# LED_PORT.net
KiCad netlist of a schematic drawn in Altium Designer
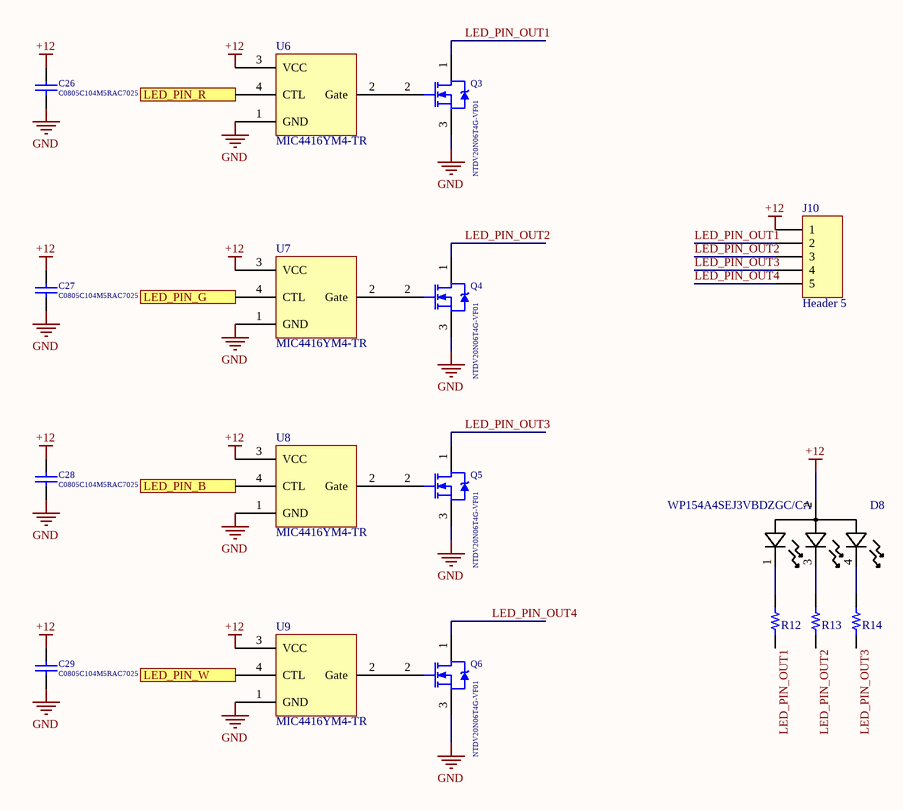
[diagram p0: LED_PORT.SchDoc]

(export (version "E")
  (design (tool "Eeschema 10.0.6"))
  (components
    (comp (ref "C26")
      (value "C0805C104M5RAC7025")
      (footprint "CAP SMD 0805")
      (description "0.1 µF ±20% 50V Ceramic Capacitor X7R 0805 (2012 Metric)")
      (fields (field (name "PUBLISHER") "Altium Limited"))
      (libsource (lib "DIY-USB Led Controller") (part "Cap_3_1"))
    )
    (comp (ref "C27")
      (value "C0805C104M5RAC7025")
      (footprint "CAP SMD 0805")
      (description "0.1 µF ±20% 50V Ceramic Capacitor X7R 0805 (2012 Metric)")
      (fields (field (name "PUBLISHER") "Altium Limited"))
      (libsource (lib "DIY-USB Led Controller") (part "Cap_3_1"))
    )
    (comp (ref "C28")
      (value "C0805C104M5RAC7025")
      (footprint "CAP SMD 0805")
      (description "0.1 µF ±20% 50V Ceramic Capacitor X7R 0805 (2012 Metric)")
      (fields (field (name "PUBLISHER") "Altium Limited"))
      (libsource (lib "DIY-USB Led Controller") (part "Cap_3_1"))
    )
    (comp (ref "C29")
      (value "C0805C104M5RAC7025")
      (footprint "CAP SMD 0805")
      (description "0.1 µF ±20% 50V Ceramic Capacitor X7R 0805 (2012 Metric)")
      (fields (field (name "PUBLISHER") "Altium Limited"))
      (libsource (lib "DIY-USB Led Controller") (part "Cap_3_1"))
    )
    (comp (ref "D8")
      (value "WP154A4SEJ3VBDZGC/CA")
      (footprint "LED_RGB_5MM")
      (description "5mm RGB Tri-Color Round Lamp")
      (fields (field (name "COPYRIGHT") "Copyright (C) 2022 Ultra Librarian. All rights reserved."))
      (libsource (lib "WP154A4SEJ3VBDZGC&slash_CA") (part "WP154A4SEJ3VBDZGC/CA"))
    )
    (comp (ref "J10")
      (value "Header 5")
      (footprint "CONN. 5")
      (fields (field (name "PUBLISHER") "Altium Limited"))
      (libsource (lib "DIY-USB Led Controller") (part "TermBlock 5"))
    )
    (comp (ref "Q3")
      (value "NTDV20N06T4G-VF01")
      (footprint "DPAK228P991X238-3N")
      (description "MOSFET N-CH 60V 20A DPAK")
      (fields
        (field (name "MANUFACTURE PART NUMBER") "IRF540N_R4942")
        (field (name "PUBLISHER") "Altium Limited")
      )
      (libsource (lib "HYD_EMER_2") (part "IRF540NS"))
    )
    (comp (ref "Q4")
      (value "NTDV20N06T4G-VF01")
      (footprint "DPAK228P991X238-3N")
      (description "MOSFET N-CH 60V 20A DPAK")
      (fields
        (field (name "MANUFACTURE PART NUMBER") "IRF540N_R4942")
        (field (name "PUBLISHER") "Altium Limited")
      )
      (libsource (lib "HYD_EMER_2") (part "IRF540NS"))
    )
    (comp (ref "Q5")
      (value "NTDV20N06T4G-VF01")
      (footprint "DPAK228P991X238-3N")
      (description "MOSFET N-CH 60V 20A DPAK")
      (fields
        (field (name "MANUFACTURE PART NUMBER") "IRF540N_R4942")
        (field (name "PUBLISHER") "Altium Limited")
      )
      (libsource (lib "HYD_EMER_2") (part "IRF540NS"))
    )
    (comp (ref "Q6")
      (value "NTDV20N06T4G-VF01")
      (footprint "DPAK228P991X238-3N")
      (description "MOSFET N-CH 60V 20A DPAK")
      (fields
        (field (name "MANUFACTURE PART NUMBER") "IRF540N_R4942")
        (field (name "PUBLISHER") "Altium Limited")
      )
      (libsource (lib "HYD_EMER_2") (part "IRF540NS"))
    )
    (comp (ref "R12")
      (value "1k")
      (footprint "RES SMD 0805")
      (description "RES SMD 1k OHM 1% 1/4W 0805")
      (libsource (lib "DIY-USB Led Controller") (part "RESISTOR"))
    )
    (comp (ref "R13")
      (value "1K")
      (footprint "RES SMD 0805")
      (description "RES SMD 1K OHM 1% 1/4W 0805")
      (libsource (lib "DIY-USB Led Controller") (part "RESISTOR_2"))
    )
    (comp (ref "R14")
      (value "1K")
      (footprint "RES SMD 0805")
      (description "RES SMD 1K OHM 1% 1/4W 0805")
      (libsource (lib "DIY-USB Led Controller") (part "RESISTOR_2"))
    )
    (comp (ref "U6")
      (value "MIC4416YM4-TR")
      (footprint "MICROCHIP SOT-143-4")
      (description "IC GATE DRVR LOW-SIDE SOT143")
      (fields (field (name "MANUFACTURER") "Microchip Technology"))
      (libsource (lib "Celestial Altium Library - altium_library") (part "MICROCHIP MIC4416"))
    )
    (comp (ref "U7")
      (value "MIC4416YM4-TR")
      (footprint "MICROCHIP SOT-143-4")
      (description "IC GATE DRVR LOW-SIDE SOT143")
      (fields (field (name "MANUFACTURER") "Microchip Technology"))
      (libsource (lib "Celestial Altium Library - altium_library") (part "MICROCHIP MIC4416"))
    )
    (comp (ref "U8")
      (value "MIC4416YM4-TR")
      (footprint "MICROCHIP SOT-143-4")
      (description "IC GATE DRVR LOW-SIDE SOT143")
      (fields (field (name "MANUFACTURER") "Microchip Technology"))
      (libsource (lib "Celestial Altium Library - altium_library") (part "MICROCHIP MIC4416"))
    )
    (comp (ref "U9")
      (value "MIC4416YM4-TR")
      (footprint "MICROCHIP SOT-143-4")
      (description "IC GATE DRVR LOW-SIDE SOT143")
      (fields (field (name "MANUFACTURER") "Microchip Technology"))
      (libsource (lib "Celestial Altium Library - altium_library") (part "MICROCHIP MIC4416"))
    )
  )
  (nets
    (net (code "1") (name "+12") (class "Default")
      (node (ref "C26") (pin "2") (pinfunction "2_2") (pintype "passive"))
      (node (ref "C27") (pin "2") (pinfunction "2_2") (pintype "passive"))
      (node (ref "C28") (pin "2") (pinfunction "2_2") (pintype "passive"))
      (node (ref "C29") (pin "2") (pinfunction "2_2") (pintype "passive"))
      (node (ref "D8") (pin "2") (pinfunction "2_2") (pintype "passive"))
      (node (ref "J10") (pin "1") (pinfunction "1_1") (pintype "passive"))
      (node (ref "U6") (pin "3") (pinfunction "VCC_3") (pintype "passive"))
      (node (ref "U7") (pin "3") (pinfunction "VCC_3") (pintype "passive"))
      (node (ref "U8") (pin "3") (pinfunction "VCC_3") (pintype "passive"))
      (node (ref "U9") (pin "3") (pinfunction "VCC_3") (pintype "passive"))
    )
    (net (code "2") (name "/LED_PIN_B") (class "Default")
      (node (ref "U8") (pin "4") (pinfunction "CTL_4") (pintype "passive"))
    )
    (net (code "3") (name "/LED_PIN_G") (class "Default")
      (node (ref "U7") (pin "4") (pinfunction "CTL_4") (pintype "passive"))
    )
    (net (code "4") (name "/LED_PIN_OUT1") (class "Default")
      (node (ref "J10") (pin "2") (pinfunction "2_2") (pintype "passive"))
      (node (ref "Q3") (pin "1") (pinfunction "D_1") (pintype "passive"))
      (node (ref "R12") (pin "1") (pinfunction "1_1") (pintype "passive"))
    )
    (net (code "5") (name "/LED_PIN_OUT2") (class "Default")
      (node (ref "J10") (pin "3") (pinfunction "3_3") (pintype "passive"))
      (node (ref "Q4") (pin "1") (pinfunction "D_1") (pintype "passive"))
      (node (ref "R13") (pin "1") (pinfunction "1_1") (pintype "passive"))
    )
    (net (code "6") (name "/LED_PIN_OUT3") (class "Default")
      (node (ref "J10") (pin "4") (pinfunction "4_4") (pintype "passive"))
      (node (ref "Q5") (pin "1") (pinfunction "D_1") (pintype "passive"))
      (node (ref "R14") (pin "1") (pinfunction "1_1") (pintype "passive"))
    )
    (net (code "7") (name "/LED_PIN_OUT4") (class "Default")
      (node (ref "J10") (pin "5") (pinfunction "5_5") (pintype "passive"))
      (node (ref "Q6") (pin "1") (pinfunction "D_1") (pintype "passive"))
    )
    (net (code "8") (name "/LED_PIN_R") (class "Default")
      (node (ref "U6") (pin "4") (pinfunction "CTL_4") (pintype "passive"))
    )
    (net (code "9") (name "/LED_PIN_W") (class "Default")
      (node (ref "U9") (pin "4") (pinfunction "CTL_4") (pintype "passive"))
    )
    (net (code "10") (name "GND") (class "Default")
      (node (ref "C26") (pin "1") (pinfunction "1_1") (pintype "passive"))
      (node (ref "C27") (pin "1") (pinfunction "1_1") (pintype "passive"))
      (node (ref "C28") (pin "1") (pinfunction "1_1") (pintype "passive"))
      (node (ref "C29") (pin "1") (pinfunction "1_1") (pintype "passive"))
      (node (ref "Q3") (pin "3") (pinfunction "S_3") (pintype "passive"))
      (node (ref "Q4") (pin "3") (pinfunction "S_3") (pintype "passive"))
      (node (ref "Q5") (pin "3") (pinfunction "S_3") (pintype "passive"))
      (node (ref "Q6") (pin "3") (pinfunction "S_3") (pintype "passive"))
      (node (ref "U6") (pin "1") (pinfunction "GND_1") (pintype "passive"))
      (node (ref "U7") (pin "1") (pinfunction "GND_1") (pintype "passive"))
      (node (ref "U8") (pin "1") (pinfunction "GND_1") (pintype "passive"))
      (node (ref "U9") (pin "1") (pinfunction "GND_1") (pintype "passive"))
    )
    (net (code "11") (name "Net-(D8-Pad1)") (class "Default")
      (node (ref "D8") (pin "1") (pinfunction "1_1") (pintype "passive"))
      (node (ref "R12") (pin "2") (pinfunction "2_2") (pintype "passive"))
    )
    (net (code "12") (name "Net-(D8-Pad3)") (class "Default")
      (node (ref "D8") (pin "3") (pinfunction "3_3") (pintype "passive"))
      (node (ref "R13") (pin "2") (pinfunction "2_2") (pintype "passive"))
    )
    (net (code "13") (name "Net-(D8-Pad4)") (class "Default")
      (node (ref "D8") (pin "4") (pinfunction "4_4") (pintype "passive"))
      (node (ref "R14") (pin "2") (pinfunction "2_2") (pintype "passive"))
    )
    (net (code "14") (name "Net-(Q3-G)") (class "Default")
      (node (ref "Q3") (pin "2") (pinfunction "G_2") (pintype "passive"))
      (node (ref "U6") (pin "2") (pinfunction "Gate_2") (pintype "passive"))
    )
    (net (code "15") (name "Net-(Q4-G)") (class "Default")
      (node (ref "Q4") (pin "2") (pinfunction "G_2") (pintype "passive"))
      (node (ref "U7") (pin "2") (pinfunction "Gate_2") (pintype "passive"))
    )
    (net (code "16") (name "Net-(Q5-G)") (class "Default")
      (node (ref "Q5") (pin "2") (pinfunction "G_2") (pintype "passive"))
      (node (ref "U8") (pin "2") (pinfunction "Gate_2") (pintype "passive"))
    )
    (net (code "17") (name "Net-(Q6-G)") (class "Default")
      (node (ref "Q6") (pin "2") (pinfunction "G_2") (pintype "passive"))
      (node (ref "U9") (pin "2") (pinfunction "Gate_2") (pintype "passive"))
    )
  )
)
